# Deckelplatine.net
KiCad netlist of a schematic drawn in EAGLE
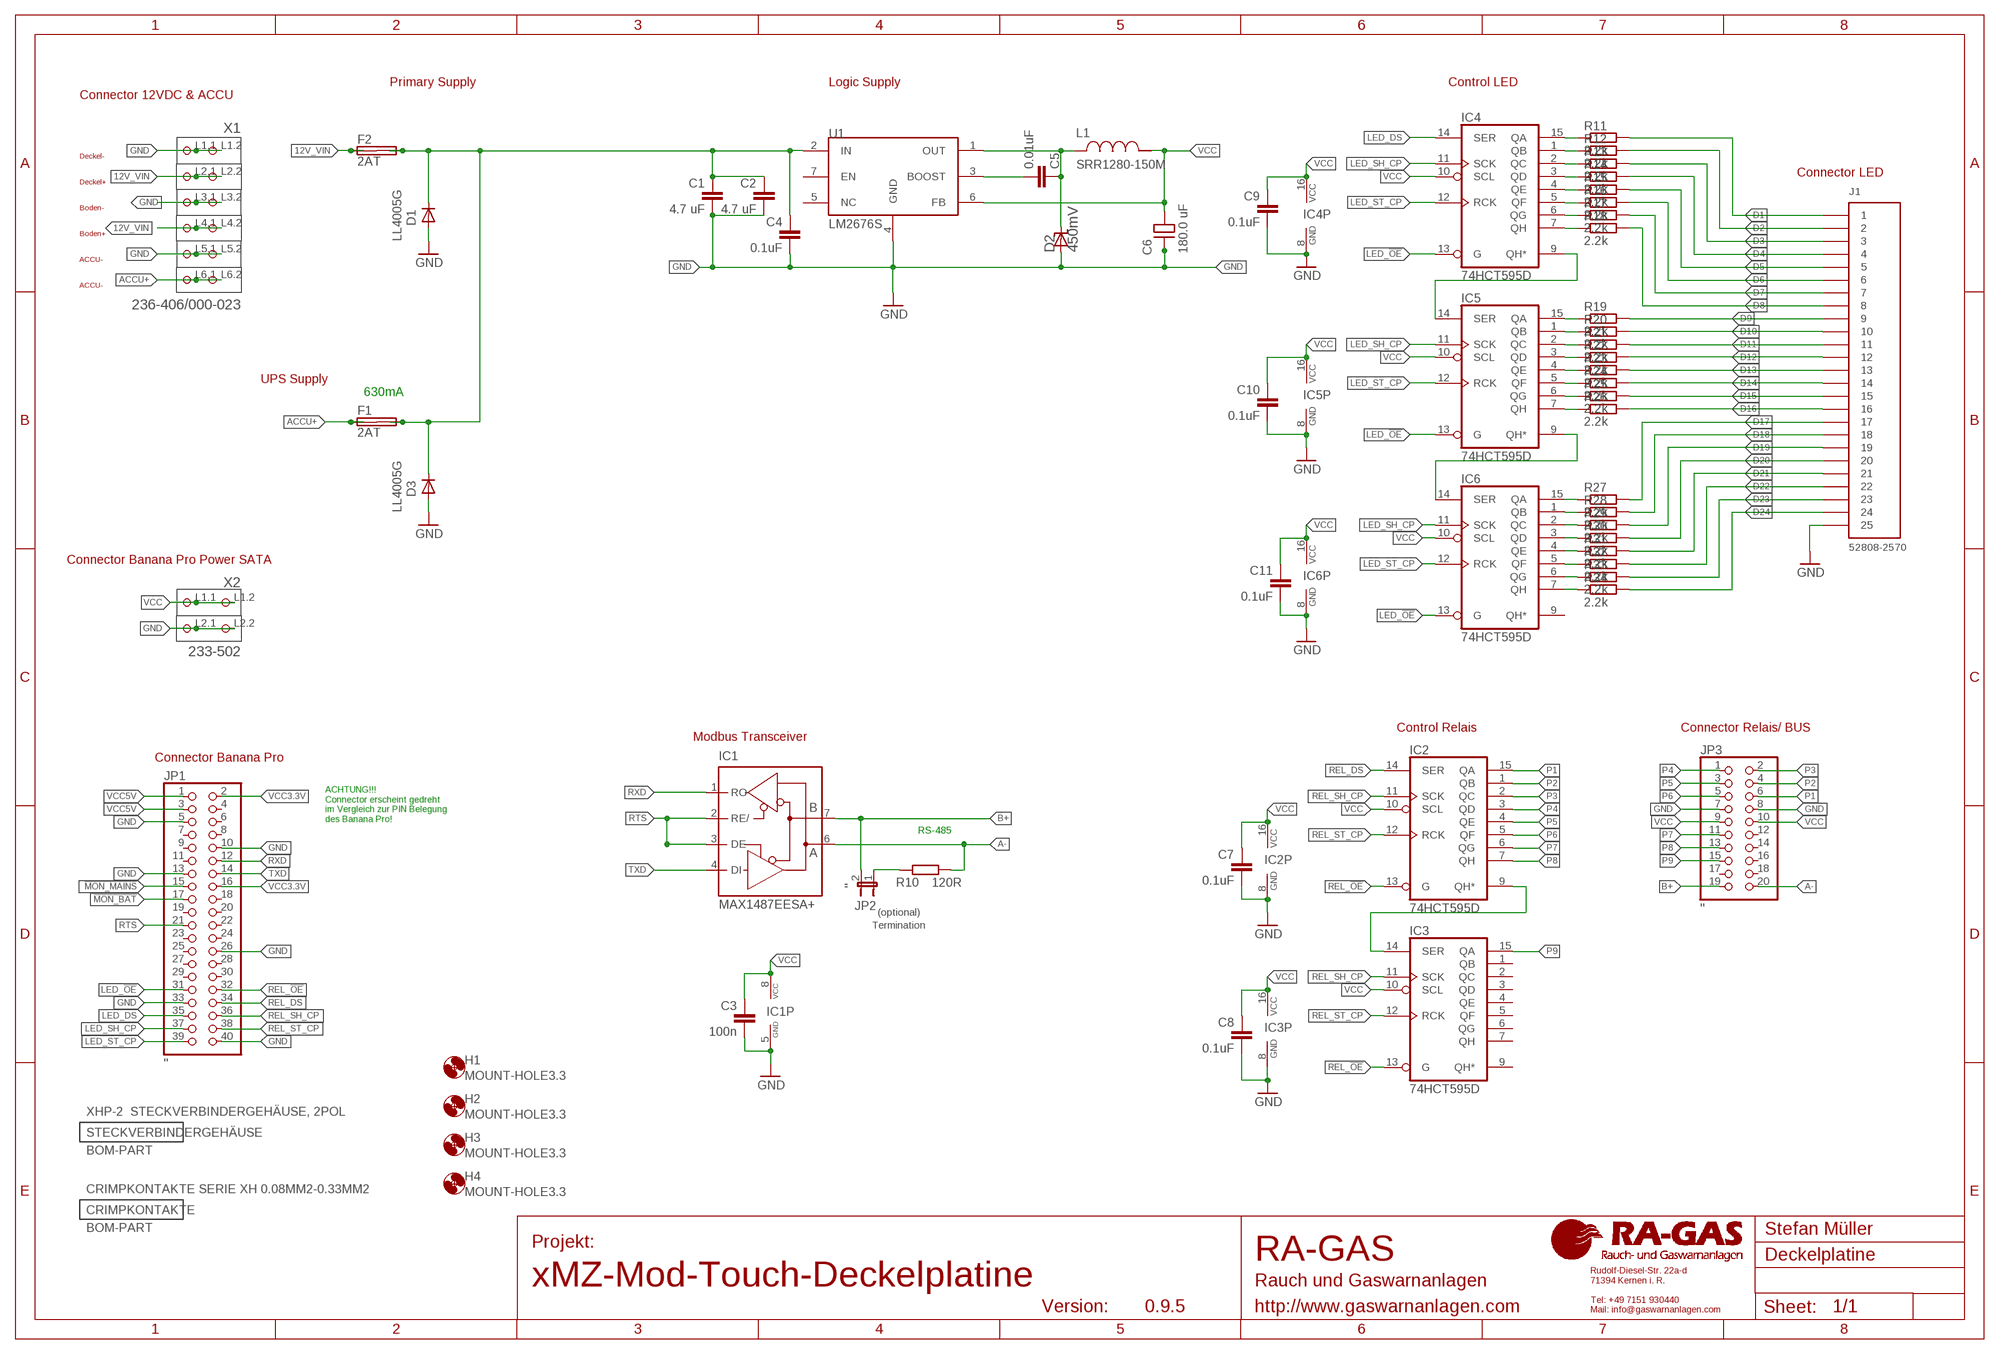
[diagram p0: schematic, sheet 1]

(export (version "E")
  (design (tool "Eeschema 10.0.6"))
  (components
    (comp (ref "C1")
      (value "4.7 uF")
      (footprint "eagle-import:GRM21BR61E475MA12L")
      (fields (field (name "MANUFACTURER_PART_NUMBER") "GRM21BR61E475MA12L") (field (name "MF") "MURATA"))
      (libsource (lib "eagle-import") (part "GRM21BR61E475MA12L"))
    )
    (comp (ref "C2")
      (value "4.7 uF")
      (footprint "eagle-import:GRM21BR61E475MA12L")
      (fields (field (name "MANUFACTURER_PART_NUMBER") "GRM21BR61E475MA12L") (field (name "MF") "MURATA"))
      (libsource (lib "eagle-import") (part "GRM21BR61E475MA12L"))
    )
    (comp (ref "C3")
      (value "100n")
      (footprint "eagle-import:C0603")
      (fields
        (field (name "MF") "KEMET")
        (field (name "MPN") "C0603C104K8RACTU")
        (field (name "PARTNO") "ECHU-16-100N")
      )
      (libsource (lib "eagle-import") (part "C-EUC0603"))
    )
    (comp (ref "C4")
      (value "0.1uF")
      (footprint "eagle-import:0805")
      (fields (field (name "MANUFACTURER_PART_NUMBER") "08053C104KAT2A") (field (name "MF") "AVX"))
      (libsource (lib "eagle-import") (part "08053C104KAT2A"))
    )
    (comp (ref "C5")
      (value "0.01uF")
      (footprint "eagle-import:GRM216R71H103KA01D")
      (fields (field (name "MANUFACTURER_PART_NUMBER") "GRM216R71H103KA01D") (field (name "MF") "MURATA"))
      (libsource (lib "eagle-import") (part "GRM216R71H103KA01D"))
    )
    (comp (ref "C6")
      (value "180.0 uF")
      (footprint "eagle-import:SM_RADIAL_10MM")
      (fields
        (field (name "MF") "PANASONIC ELECTRONIC COMPONENTS")
        (field (name "MPN") "16SVP180MX")
        (field (name "PARTNO") "RAD FC 560/35")
      )
      (libsource (lib "eagle-import") (part "16SVP180MSM_RADIAL_10MM"))
    )
    (comp (ref "C7")
      (value "0.1uF")
      (footprint "eagle-import:C0603")
      (fields
        (field (name "MF") "KEMET")
        (field (name "MPN") "C0603C104K8RACTU")
        (field (name "PARTNO") "SMD TAN.0,1/35")
      )
      (libsource (lib "eagle-import") (part "C-EUC0603"))
    )
    (comp (ref "C8")
      (value "0.1uF")
      (footprint "eagle-import:C0603")
      (fields
        (field (name "MF") "KEMET")
        (field (name "MPN") "C0603C104K8RACTU")
        (field (name "PARTNO") "SMD TAN.0,1/35")
      )
      (libsource (lib "eagle-import") (part "C-EUC0603"))
    )
    (comp (ref "C9")
      (value "0.1uF")
      (footprint "eagle-import:C0603")
      (fields
        (field (name "MF") "KEMET")
        (field (name "MPN") "C0603C104K8RACTU")
        (field (name "PARTNO") "SMD TAN.0,1/35")
      )
      (libsource (lib "eagle-import") (part "C-EUC0603"))
    )
    (comp (ref "C10")
      (value "0.1uF")
      (footprint "eagle-import:C0603")
      (fields
        (field (name "MF") "KEMET")
        (field (name "MPN") "C0603C104K8RACTU")
        (field (name "PARTNO") "SMD TAN.0,1/35")
      )
      (libsource (lib "eagle-import") (part "C-EUC0603"))
    )
    (comp (ref "C11")
      (value "0.1uF")
      (footprint "eagle-import:C0603")
      (fields
        (field (name "MF") "KEMET")
        (field (name "MPN") "C0603C104K8RACTU")
        (field (name "PARTNO") "SMD TAN.0,1/35")
      )
      (libsource (lib "eagle-import") (part "C-EUC0603"))
    )
    (comp (ref "D1")
      (value "LL4005G")
      (footprint "eagle-import:MELF-MLL41")
      (fields (field (name "MF") "TAIWAN SEMICONDUCTOR"))
      (libsource (lib "eagle-import") (part "DIODE-MELF-MLL41"))
    )
    (comp (ref "D2")
      (value "450mV")
      (footprint "eagle-import:SMB")
      (fields (field (name "MANUFACTURER_PART_NUMBER") "B340LB-13-F") (field (name "MF") "DIODES INC."))
      (libsource (lib "eagle-import") (part "B340LB-13-F"))
    )
    (comp (ref "D3")
      (value "LL4005G")
      (footprint "eagle-import:MELF-MLL41")
      (fields (field (name "MF") "TAIWAN SEMICONDUCTOR"))
      (libsource (lib "eagle-import") (part "DIODE-MELF-MLL41"))
    )
    (comp (ref "F1")
      (value "2AT")
      (footprint "eagle-import:01110005MR")
      (fields (field (name "MF") "LITTELFUSE") (field (name "MPN") "01110005MR"))
      (libsource (lib "eagle-import") (part "01110005MR"))
    )
    (comp (ref "F2")
      (value "2AT")
      (footprint "eagle-import:01110005MR")
      (fields (field (name "MF") "LITTELFUSE") (field (name "MPN") "01110005MR"))
      (libsource (lib "eagle-import") (part "01110005MR"))
    )
    (comp (ref "H1")
      (value "MOUNT-HOLE3.3")
      (footprint "eagle-import:3,3")
      (libsource (lib "eagle-import") (part "MOUNT-HOLE3.3"))
    )
    (comp (ref "H2")
      (value "MOUNT-HOLE3.3")
      (footprint "eagle-import:3,3")
      (libsource (lib "eagle-import") (part "MOUNT-HOLE3.3"))
    )
    (comp (ref "H3")
      (value "MOUNT-HOLE3.3")
      (footprint "eagle-import:3,3")
      (libsource (lib "eagle-import") (part "MOUNT-HOLE3.3"))
    )
    (comp (ref "H4")
      (value "MOUNT-HOLE3.3")
      (footprint "eagle-import:3,3")
      (libsource (lib "eagle-import") (part "MOUNT-HOLE3.3"))
    )
    (comp (ref "IC1")
      (value "MAX1487EESA+")
      (footprint "eagle-import:SO08")
      (fields
        (field (name "MF") "MAXIM")
        (field (name "MPN") "MAX481CSA")
        (field (name "MF_1") "MAXIM INTEGRATED PRODUCTS")
        (field (name "MPN_1") "MAX1487EESA+")
        (field (name "OC_FARNELL") "1593310")
        (field (name "PARTNO") "MAX481CSA")
      )
      (libsource (lib "eagle-import") (part "MAX481CSA"))
    )
    (comp (ref "IC2")
      (value "74HCT595D")
      (footprint "eagle-import:SO16")
      (fields
        (field (name "MF") "NXP")
        (field (name "PARTNO") "SMD HC 595")
        (field (name "MPN") "74HCT595D")
        (field (name "OC_FARNELL") "2098004")
      )
      (libsource (lib "eagle-import") (part "74595DHCT"))
    )
    (comp (ref "IC3")
      (value "74HCT595D")
      (footprint "eagle-import:SO16")
      (fields
        (field (name "MF") "NXP")
        (field (name "MPN") "74HCT595D")
        (field (name "OC_FARNELL") "2098004")
        (field (name "PARTNO") "SMD HC 595")
      )
      (libsource (lib "eagle-import") (part "74595DHCT"))
    )
    (comp (ref "IC4")
      (value "74HCT595D")
      (footprint "eagle-import:SO16")
      (fields
        (field (name "MF") "NXP")
        (field (name "MPN") "74HCT595D")
        (field (name "OC_FARNELL") "2098004")
        (field (name "PARTNO") "SMD HC 595")
      )
      (libsource (lib "eagle-import") (part "74595DHCT"))
    )
    (comp (ref "IC5")
      (value "74HCT595D")
      (footprint "eagle-import:SO16")
      (fields
        (field (name "MF") "NXP")
        (field (name "MPN") "74HCT595D")
        (field (name "OC_FARNELL") "2098004")
        (field (name "PARTNO") "SMD HC 595")
      )
      (libsource (lib "eagle-import") (part "74595DHCT"))
    )
    (comp (ref "IC6")
      (value "74HCT595D")
      (footprint "eagle-import:SO16")
      (fields
        (field (name "MF") "NXP")
        (field (name "MPN") "74HCT595D")
        (field (name "OC_FARNELL") "2098004")
        (field (name "PARTNO") "SMD HC 595")
      )
      (libsource (lib "eagle-import") (part "74595DHCT"))
    )
    (comp (ref "J1")
      (value "52808-2570")
      (footprint "eagle-import:52808-2570")
      (fields (field (name "MF") "MOLEX"))
      (libsource (lib "eagle-import") (part "52808-2570"))
    )
    (comp (ref "JP1")
      (value "''")
      (footprint "eagle-import:2X20")
      (fields (field (name "MF") "HARWIN") (field (name "MPN") "M20-6112045"))
      (libsource (lib "eagle-import") (part "PINHD-2X20"))
    )
    (comp (ref "JP2")
      (value "''")
      (footprint "eagle-import:JP1")
      (fields (field (name "MF") "TE CONNECTIVITY / AMP") (field (name "MPN") "825433-2"))
      (libsource (lib "eagle-import") (part "JP1E"))
    )
    (comp (ref "JP3")
      (value "''")
      (footprint "eagle-import:2X10")
      (fields (field (name "MF") "TE CONNECTIVITY / AMP") (field (name "MPN") "5103308-5"))
      (libsource (lib "eagle-import") (part "PINHD-2X10"))
    )
    (comp (ref "L1")
      (value "SRR1280-150M")
      (footprint "eagle-import:SRR1280")
      (fields (field (name "MF") "COILCRAFT") (field (name "MPN") "MSS1278-153MLD"))
      (libsource (lib "eagle-import") (part "SRR1280-150M"))
    )
    (comp (ref "R10")
      (value "120R")
      (footprint "eagle-import:R1206")
      (fields (field (name "MF") "TE CONNECTIVITY") (field (name "MPN") "CRGH1206F120R"))
      (libsource (lib "eagle-import") (part "rcl_R-EU_R1206"))
    )
    (comp (ref "R11")
      (value "2.2k")
      (footprint "eagle-import:R0603")
      (fields
        (field (name "MF") "YAGEO (PHYCOMP)")
        (field (name "MPN") "RC0603FR-072K2L")
        (field (name "PARTNO") "SMD-0603 2,2K")
      )
      (libsource (lib "eagle-import") (part "R-EU_R0603"))
    )
    (comp (ref "R12")
      (value "2.2k")
      (footprint "eagle-import:R0603")
      (fields
        (field (name "MF") "YAGEO (PHYCOMP)")
        (field (name "MPN") "RC0603FR-072K2L")
        (field (name "PARTNO") "SMD-0603 2,2K")
      )
      (libsource (lib "eagle-import") (part "R-EU_R0603"))
    )
    (comp (ref "R13")
      (value "2.2k")
      (footprint "eagle-import:R0603")
      (fields
        (field (name "MF") "YAGEO (PHYCOMP)")
        (field (name "MPN") "RC0603FR-072K2L")
        (field (name "PARTNO") "SMD-0603 2,2K")
      )
      (libsource (lib "eagle-import") (part "R-EU_R0603"))
    )
    (comp (ref "R14")
      (value "2.2k")
      (footprint "eagle-import:R0603")
      (fields
        (field (name "MF") "YAGEO (PHYCOMP)")
        (field (name "MPN") "RC0603FR-072K2L")
        (field (name "PARTNO") "SMD-0603 2,2K")
      )
      (libsource (lib "eagle-import") (part "R-EU_R0603"))
    )
    (comp (ref "R15")
      (value "2.2k")
      (footprint "eagle-import:R0603")
      (fields
        (field (name "MF") "YAGEO (PHYCOMP)")
        (field (name "MPN") "RC0603FR-072K2L")
        (field (name "PARTNO") "SMD-0603 2,2K")
      )
      (libsource (lib "eagle-import") (part "R-EU_R0603"))
    )
    (comp (ref "R16")
      (value "2.2k")
      (footprint "eagle-import:R0603")
      (fields
        (field (name "MF") "YAGEO (PHYCOMP)")
        (field (name "MPN") "RC0603FR-072K2L")
        (field (name "PARTNO") "SMD-0603 2,2K")
      )
      (libsource (lib "eagle-import") (part "R-EU_R0603"))
    )
    (comp (ref "R17")
      (value "2.2k")
      (footprint "eagle-import:R0603")
      (fields
        (field (name "MF") "YAGEO (PHYCOMP)")
        (field (name "MPN") "RC0603FR-072K2L")
        (field (name "PARTNO") "SMD-0603 2,2K")
      )
      (libsource (lib "eagle-import") (part "R-EU_R0603"))
    )
    (comp (ref "R18")
      (value "2.2k")
      (footprint "eagle-import:R0603")
      (fields
        (field (name "MF") "YAGEO (PHYCOMP)")
        (field (name "MPN") "RC0603FR-072K2L")
        (field (name "PARTNO") "SMD-0603 2,2K")
      )
      (libsource (lib "eagle-import") (part "R-EU_R0603"))
    )
    (comp (ref "R19")
      (value "2.2k")
      (footprint "eagle-import:R0603")
      (fields
        (field (name "MF") "YAGEO (PHYCOMP)")
        (field (name "MPN") "RC0603FR-072K2L")
        (field (name "PARTNO") "SMD-0603 2,2K")
      )
      (libsource (lib "eagle-import") (part "R-EU_R0603"))
    )
    (comp (ref "R20")
      (value "2.2k")
      (footprint "eagle-import:R0603")
      (fields
        (field (name "MF") "YAGEO (PHYCOMP)")
        (field (name "MPN") "RC0603FR-072K2L")
        (field (name "PARTNO") "SMD-0603 2,2K")
      )
      (libsource (lib "eagle-import") (part "R-EU_R0603"))
    )
    (comp (ref "R21")
      (value "2.2k")
      (footprint "eagle-import:R0603")
      (fields
        (field (name "MF") "YAGEO (PHYCOMP)")
        (field (name "MPN") "RC0603FR-072K2L")
        (field (name "PARTNO") "SMD-0603 2,2K")
      )
      (libsource (lib "eagle-import") (part "R-EU_R0603"))
    )
    (comp (ref "R22")
      (value "2.2k")
      (footprint "eagle-import:R0603")
      (fields
        (field (name "MF") "YAGEO (PHYCOMP)")
        (field (name "MPN") "RC0603FR-072K2L")
        (field (name "PARTNO") "SMD-0603 2,2K")
      )
      (libsource (lib "eagle-import") (part "R-EU_R0603"))
    )
    (comp (ref "R23")
      (value "2.2k")
      (footprint "eagle-import:R0603")
      (fields
        (field (name "MF") "YAGEO (PHYCOMP)")
        (field (name "MPN") "RC0603FR-072K2L")
        (field (name "PARTNO") "SMD-0603 2,2K")
      )
      (libsource (lib "eagle-import") (part "R-EU_R0603"))
    )
    (comp (ref "R24")
      (value "2.2k")
      (footprint "eagle-import:R0603")
      (fields
        (field (name "MF") "YAGEO (PHYCOMP)")
        (field (name "MPN") "RC0603FR-072K2L")
        (field (name "PARTNO") "SMD-0603 2,2K")
      )
      (libsource (lib "eagle-import") (part "R-EU_R0603"))
    )
    (comp (ref "R25")
      (value "2.2k")
      (footprint "eagle-import:R0603")
      (fields
        (field (name "MF") "YAGEO (PHYCOMP)")
        (field (name "MPN") "RC0603FR-072K2L")
        (field (name "PARTNO") "SMD-0603 2,2K")
      )
      (libsource (lib "eagle-import") (part "R-EU_R0603"))
    )
    (comp (ref "R26")
      (value "2.2k")
      (footprint "eagle-import:R0603")
      (fields
        (field (name "MF") "YAGEO (PHYCOMP)")
        (field (name "MPN") "RC0603FR-072K2L")
        (field (name "PARTNO") "SMD-0603 2,2K")
      )
      (libsource (lib "eagle-import") (part "R-EU_R0603"))
    )
    (comp (ref "R27")
      (value "2.2k")
      (footprint "eagle-import:R0603")
      (fields
        (field (name "MF") "YAGEO (PHYCOMP)")
        (field (name "MPN") "RC0603FR-072K2L")
        (field (name "PARTNO") "SMD-0603 2,2K")
      )
      (libsource (lib "eagle-import") (part "R-EU_R0603"))
    )
    (comp (ref "R28")
      (value "2.2k")
      (footprint "eagle-import:R0603")
      (fields
        (field (name "MF") "YAGEO (PHYCOMP)")
        (field (name "MPN") "RC0603FR-072K2L")
        (field (name "PARTNO") "SMD-0603 2,2K")
      )
      (libsource (lib "eagle-import") (part "R-EU_R0603"))
    )
    (comp (ref "R29")
      (value "2.2k")
      (footprint "eagle-import:R0603")
      (fields
        (field (name "MF") "YAGEO (PHYCOMP)")
        (field (name "MPN") "RC0603FR-072K2L")
        (field (name "PARTNO") "SMD-0603 2,2K")
      )
      (libsource (lib "eagle-import") (part "R-EU_R0603"))
    )
    (comp (ref "R30")
      (value "2.2k")
      (footprint "eagle-import:R0603")
      (fields
        (field (name "MF") "YAGEO (PHYCOMP)")
        (field (name "MPN") "RC0603FR-072K2L")
        (field (name "PARTNO") "SMD-0603 2,2K")
      )
      (libsource (lib "eagle-import") (part "R-EU_R0603"))
    )
    (comp (ref "R31")
      (value "2.2k")
      (footprint "eagle-import:R0603")
      (fields
        (field (name "MF") "YAGEO (PHYCOMP)")
        (field (name "MPN") "RC0603FR-072K2L")
        (field (name "PARTNO") "SMD-0603 2,2K")
      )
      (libsource (lib "eagle-import") (part "R-EU_R0603"))
    )
    (comp (ref "R32")
      (value "2.2k")
      (footprint "eagle-import:R0603")
      (fields
        (field (name "MF") "YAGEO (PHYCOMP)")
        (field (name "MPN") "RC0603FR-072K2L")
        (field (name "PARTNO") "SMD-0603 2,2K")
      )
      (libsource (lib "eagle-import") (part "R-EU_R0603"))
    )
    (comp (ref "R33")
      (value "2.2k")
      (footprint "eagle-import:R0603")
      (fields
        (field (name "MF") "YAGEO (PHYCOMP)")
        (field (name "MPN") "RC0603FR-072K2L")
        (field (name "PARTNO") "SMD-0603 2,2K")
      )
      (libsource (lib "eagle-import") (part "R-EU_R0603"))
    )
    (comp (ref "R34")
      (value "2.2k")
      (footprint "eagle-import:R0603")
      (fields
        (field (name "MF") "YAGEO (PHYCOMP)")
        (field (name "MPN") "RC0603FR-072K2L")
        (field (name "PARTNO") "SMD-0603 2,2K")
      )
      (libsource (lib "eagle-import") (part "R-EU_R0603"))
    )
    (comp (ref "U1")
      (value "LM2676S")
      (footprint "eagle-import:TO-263-7")
      (fields (field (name "MF") "TEXAS INSTRUMENTS") (field (name "MPN") "LM2676S-5.0/NOPB"))
      (libsource (lib "eagle-import") (part "LM2676S"))
    )
    (comp (ref "X1")
      (value "236-406/000-023")
      (footprint "eagle-import:P-236-406")
      (fields (field (name "MF") "WAGO") (field (name "MPN") "236-406"))
      (libsource (lib "eagle-import") (part "236-406/000-023"))
    )
    (comp (ref "X2")
      (value "233-502")
      (footprint "eagle-import:P-233-502")
      (fields (field (name "MF") "WAGO") (field (name "MPN") "233-502."))
      (libsource (lib "eagle-import") (part "233-502"))
    )
  )
  (nets
    (net (code "1") (name "/LED_~{OE}") (class "Default")
      (node (ref "IC4") (pin "13") (pinfunction "G_13") (pintype "input"))
      (node (ref "IC5") (pin "13") (pinfunction "G_13") (pintype "input"))
      (node (ref "IC6") (pin "13") (pinfunction "G_13") (pintype "input"))
      (node (ref "JP1") (pin "31") (pinfunction "31_31") (pintype "passive"))
    )
    (net (code "2") (name "/REL_~{OE}") (class "Default")
      (node (ref "IC2") (pin "13") (pinfunction "G_13") (pintype "input"))
      (node (ref "IC3") (pin "13") (pinfunction "G_13") (pintype "input"))
      (node (ref "JP1") (pin "32") (pinfunction "32_32") (pintype "passive"))
    )
    (net (code "3") (name "/~{MON_BAT}") (class "Default")
      (node (ref "JP1") (pin "17") (pinfunction "17_17") (pintype "passive"))
    )
    (net (code "4") (name "/~{MON_MAINS}") (class "Default")
      (node (ref "JP1") (pin "15") (pinfunction "15_15") (pintype "passive"))
    )
    (net (code "5") (name "12V_VIN") (class "Default")
      (node (ref "F2") (pin "1A") (pinfunction "1A_1A") (pintype "passive"))
      (node (ref "F2") (pin "1B") (pinfunction "1B_1B") (pintype "passive"))
      (node (ref "X1") (pin "L2.1") (pinfunction "P2.1_L2.1") (pintype "bidirectional"))
      (node (ref "X1") (pin "L2.2") (pinfunction "P2.2_L2.2") (pintype "bidirectional"))
      (node (ref "X1") (pin "L4.1") (pinfunction "P4.1_L4.1") (pintype "bidirectional"))
      (node (ref "X1") (pin "L4.2") (pinfunction "P4.2_L4.2") (pintype "bidirectional"))
    )
    (net (code "6") (name "A-") (class "Default")
      (node (ref "IC1") (pin "6") (pinfunction "A_6") (pintype "passive"))
      (node (ref "JP3") (pin "20") (pinfunction "20_20") (pintype "passive"))
      (node (ref "R10") (pin "2") (pinfunction "2_2") (pintype "passive"))
    )
    (net (code "7") (name "ACCU+") (class "Default")
      (node (ref "F1") (pin "1A") (pinfunction "1A_1A") (pintype "passive"))
      (node (ref "F1") (pin "1B") (pinfunction "1B_1B") (pintype "passive"))
      (node (ref "X1") (pin "L6.1") (pinfunction "P6.1_L6.1") (pintype "bidirectional"))
      (node (ref "X1") (pin "L6.2") (pinfunction "P6.2_L6.2") (pintype "bidirectional"))
    )
    (net (code "8") (name "B+") (class "Default")
      (node (ref "IC1") (pin "7") (pinfunction "B_7") (pintype "passive"))
      (node (ref "JP2") (pin "2") (pinfunction "2_2") (pintype "passive"))
      (node (ref "JP3") (pin "19") (pinfunction "19_19") (pintype "passive"))
    )
    (net (code "9") (name "D1") (class "Default")
      (node (ref "J1") (pin "1") (pinfunction "1_1") (pintype "bidirectional"))
      (node (ref "R11") (pin "2") (pinfunction "2_2") (pintype "passive"))
    )
    (net (code "10") (name "D2") (class "Default")
      (node (ref "J1") (pin "2") (pinfunction "2_2") (pintype "bidirectional"))
      (node (ref "R12") (pin "2") (pinfunction "2_2") (pintype "passive"))
    )
    (net (code "11") (name "D3") (class "Default")
      (node (ref "J1") (pin "3") (pinfunction "3_3") (pintype "bidirectional"))
      (node (ref "R13") (pin "2") (pinfunction "2_2") (pintype "passive"))
    )
    (net (code "12") (name "D4") (class "Default")
      (node (ref "J1") (pin "4") (pinfunction "4_4") (pintype "bidirectional"))
      (node (ref "R14") (pin "2") (pinfunction "2_2") (pintype "passive"))
    )
    (net (code "13") (name "D5") (class "Default")
      (node (ref "J1") (pin "5") (pinfunction "5_5") (pintype "bidirectional"))
      (node (ref "R15") (pin "2") (pinfunction "2_2") (pintype "passive"))
    )
    (net (code "14") (name "D6") (class "Default")
      (node (ref "J1") (pin "6") (pinfunction "6_6") (pintype "bidirectional"))
      (node (ref "R16") (pin "2") (pinfunction "2_2") (pintype "passive"))
    )
    (net (code "15") (name "D7") (class "Default")
      (node (ref "J1") (pin "7") (pinfunction "7_7") (pintype "bidirectional"))
      (node (ref "R17") (pin "2") (pinfunction "2_2") (pintype "passive"))
    )
    (net (code "16") (name "D8") (class "Default")
      (node (ref "J1") (pin "8") (pinfunction "8_8") (pintype "bidirectional"))
      (node (ref "R18") (pin "2") (pinfunction "2_2") (pintype "passive"))
    )
    (net (code "17") (name "D9") (class "Default")
      (node (ref "J1") (pin "9") (pinfunction "9_9") (pintype "bidirectional"))
      (node (ref "R19") (pin "2") (pinfunction "2_2") (pintype "passive"))
    )
    (net (code "18") (name "D10") (class "Default")
      (node (ref "J1") (pin "10") (pinfunction "10_10") (pintype "bidirectional"))
      (node (ref "R20") (pin "2") (pinfunction "2_2") (pintype "passive"))
    )
    (net (code "19") (name "D11") (class "Default")
      (node (ref "J1") (pin "11") (pinfunction "11_11") (pintype "bidirectional"))
      (node (ref "R21") (pin "2") (pinfunction "2_2") (pintype "passive"))
    )
    (net (code "20") (name "D12") (class "Default")
      (node (ref "J1") (pin "12") (pinfunction "12_12") (pintype "bidirectional"))
      (node (ref "R22") (pin "2") (pinfunction "2_2") (pintype "passive"))
    )
    (net (code "21") (name "D13") (class "Default")
      (node (ref "J1") (pin "13") (pinfunction "13_13") (pintype "bidirectional"))
      (node (ref "R23") (pin "2") (pinfunction "2_2") (pintype "passive"))
    )
    (net (code "22") (name "D14") (class "Default")
      (node (ref "J1") (pin "14") (pinfunction "14_14") (pintype "bidirectional"))
      (node (ref "R24") (pin "2") (pinfunction "2_2") (pintype "passive"))
    )
    (net (code "23") (name "D15") (class "Default")
      (node (ref "J1") (pin "15") (pinfunction "15_15") (pintype "bidirectional"))
      (node (ref "R25") (pin "2") (pinfunction "2_2") (pintype "passive"))
    )
    (net (code "24") (name "D16") (class "Default")
      (node (ref "J1") (pin "16") (pinfunction "16_16") (pintype "bidirectional"))
      (node (ref "R26") (pin "2") (pinfunction "2_2") (pintype "passive"))
    )
    (net (code "25") (name "D17") (class "Default")
      (node (ref "J1") (pin "17") (pinfunction "17_17") (pintype "bidirectional"))
      (node (ref "R27") (pin "2") (pinfunction "2_2") (pintype "passive"))
    )
    (net (code "26") (name "D18") (class "Default")
      (node (ref "J1") (pin "18") (pinfunction "18_18") (pintype "bidirectional"))
      (node (ref "R28") (pin "2") (pinfunction "2_2") (pintype "passive"))
    )
    (net (code "27") (name "D19") (class "Default")
      (node (ref "J1") (pin "19") (pinfunction "19_19") (pintype "bidirectional"))
      (node (ref "R29") (pin "2") (pinfunction "2_2") (pintype "passive"))
    )
    (net (code "28") (name "D20") (class "Default")
      (node (ref "J1") (pin "20") (pinfunction "20_20") (pintype "bidirectional"))
      (node (ref "R30") (pin "2") (pinfunction "2_2") (pintype "passive"))
    )
    (net (code "29") (name "D21") (class "Default")
      (node (ref "J1") (pin "21") (pinfunction "21_21") (pintype "bidirectional"))
      (node (ref "R31") (pin "2") (pinfunction "2_2") (pintype "passive"))
    )
    (net (code "30") (name "D22") (class "Default")
      (node (ref "J1") (pin "22") (pinfunction "22_22") (pintype "bidirectional"))
      (node (ref "R32") (pin "2") (pinfunction "2_2") (pintype "passive"))
    )
    (net (code "31") (name "D23") (class "Default")
      (node (ref "J1") (pin "23") (pinfunction "23_23") (pintype "bidirectional"))
      (node (ref "R33") (pin "2") (pinfunction "2_2") (pintype "passive"))
    )
    (net (code "32") (name "D24") (class "Default")
      (node (ref "J1") (pin "24") (pinfunction "24_24") (pintype "bidirectional"))
      (node (ref "R34") (pin "2") (pinfunction "2_2") (pintype "passive"))
    )
    (net (code "33") (name "GND") (class "Default")
      (node (ref "C1") (pin "2") (pinfunction "2_2") (pintype "passive"))
      (node (ref "C10") (pin "2") (pinfunction "2_2") (pintype "passive"))
      (node (ref "C11") (pin "2") (pinfunction "2_2") (pintype "passive"))
      (node (ref "C2") (pin "2") (pinfunction "2_2") (pintype "passive"))
      (node (ref "C3") (pin "2") (pinfunction "2_2") (pintype "passive"))
      (node (ref "C4") (pin "2") (pinfunction "2_2") (pintype "passive"))
      (node (ref "C6") (pin "2") (pinfunction "-_2") (pintype "passive"))
      (node (ref "C7") (pin "2") (pinfunction "2_2") (pintype "passive"))
      (node (ref "C8") (pin "2") (pinfunction "2_2") (pintype "passive"))
      (node (ref "C9") (pin "2") (pinfunction "2_2") (pintype "passive"))
      (node (ref "D1") (pin "A") (pinfunction "A_A") (pintype "passive"))
      (node (ref "D2") (pin "A") (pinfunction "A_A") (pintype "passive"))
      (node (ref "D3") (pin "A") (pinfunction "A_A") (pintype "passive"))
      (node (ref "IC1") (pin "5") (pinfunction "GND_5") (pintype "power_in"))
      (node (ref "IC2") (pin "8") (pinfunction "GND_8") (pintype "power_in"))
      (node (ref "IC3") (pin "8") (pinfunction "GND_8") (pintype "power_in"))
      (node (ref "IC4") (pin "8") (pinfunction "GND_8") (pintype "power_in"))
      (node (ref "IC5") (pin "8") (pinfunction "GND_8") (pintype "power_in"))
      (node (ref "IC6") (pin "8") (pinfunction "GND_8") (pintype "power_in"))
      (node (ref "J1") (pin "25") (pinfunction "25_25") (pintype "bidirectional"))
      (node (ref "JP1") (pin "10") (pinfunction "10_10") (pintype "passive"))
      (node (ref "JP1") (pin "13") (pinfunction "13_13") (pintype "passive"))
      (node (ref "JP1") (pin "26") (pinfunction "26_26") (pintype "passive"))
      (node (ref "JP1") (pin "33") (pinfunction "33_33") (pintype "passive"))
      (node (ref "JP1") (pin "40") (pinfunction "40_40") (pintype "passive"))
      (node (ref "JP1") (pin "5") (pinfunction "5_5") (pintype "passive"))
      (node (ref "JP3") (pin "7") (pinfunction "7_7") (pintype "passive"))
      (node (ref "JP3") (pin "8") (pinfunction "8_8") (pintype "passive"))
      (node (ref "U1") (pin "4") (pinfunction "GND_4") (pintype "power_in"))
      (node (ref "X1") (pin "L1.1") (pinfunction "P1.1_L1.1") (pintype "bidirectional"))
      (node (ref "X1") (pin "L1.2") (pinfunction "P1.2_L1.2") (pintype "bidirectional"))
      (node (ref "X1") (pin "L3.1") (pinfunction "P3.1_L3.1") (pintype "bidirectional"))
      (node (ref "X1") (pin "L3.2") (pinfunction "P3.2_L3.2") (pintype "bidirectional"))
      (node (ref "X1") (pin "L5.1") (pinfunction "P5.1_L5.1") (pintype "bidirectional"))
      (node (ref "X1") (pin "L5.2") (pinfunction "P5.2_L5.2") (pintype "bidirectional"))
      (node (ref "X2") (pin "L2.1") (pinfunction "P2.1_L2.1") (pintype "bidirectional"))
      (node (ref "X2") (pin "L2.2") (pinfunction "P2.2_L2.2") (pintype "bidirectional"))
    )
    (net (code "34") (name "LED_DS") (class "Default")
      (node (ref "IC4") (pin "14") (pinfunction "SER_14") (pintype "input"))
      (node (ref "JP1") (pin "35") (pinfunction "35_35") (pintype "passive"))
    )
    (net (code "35") (name "LED_SH_CP") (class "Default")
      (node (ref "IC4") (pin "11") (pinfunction "SCK_11") (pintype "input"))
      (node (ref "IC5") (pin "11") (pinfunction "SCK_11") (pintype "input"))
      (node (ref "IC6") (pin "11") (pinfunction "SCK_11") (pintype "input"))
      (node (ref "JP1") (pin "37") (pinfunction "37_37") (pintype "passive"))
    )
    (net (code "36") (name "LED_ST_CP") (class "Default")
      (node (ref "IC4") (pin "12") (pinfunction "RCK_12") (pintype "input"))
      (node (ref "IC5") (pin "12") (pinfunction "RCK_12") (pintype "input"))
      (node (ref "IC6") (pin "12") (pinfunction "RCK_12") (pintype "input"))
      (node (ref "JP1") (pin "39") (pinfunction "39_39") (pintype "passive"))
    )
    (net (code "37") (name "Net-(IC2A-QH*)") (class "Default")
      (node (ref "IC2") (pin "9") (pinfunction "QH*_9") (pintype "tri_state"))
      (node (ref "IC3") (pin "14") (pinfunction "SER_14") (pintype "input"))
    )
    (net (code "38") (name "Net-(IC4A-QA)") (class "Default")
      (node (ref "IC4") (pin "15") (pinfunction "QA_15") (pintype "tri_state"))
      (node (ref "R11") (pin "1") (pinfunction "1_1") (pintype "passive"))
    )
    (net (code "39") (name "Net-(IC4A-QB)") (class "Default")
      (node (ref "IC4") (pin "1") (pinfunction "QB_1") (pintype "tri_state"))
      (node (ref "R12") (pin "1") (pinfunction "1_1") (pintype "passive"))
    )
    (net (code "40") (name "Net-(IC4A-QC)") (class "Default")
      (node (ref "IC4") (pin "2") (pinfunction "QC_2") (pintype "tri_state"))
      (node (ref "R13") (pin "1") (pinfunction "1_1") (pintype "passive"))
    )
    (net (code "41") (name "Net-(IC4A-QD)") (class "Default")
      (node (ref "IC4") (pin "3") (pinfunction "QD_3") (pintype "tri_state"))
      (node (ref "R14") (pin "1") (pinfunction "1_1") (pintype "passive"))
    )
    (net (code "42") (name "Net-(IC4A-QE)") (class "Default")
      (node (ref "IC4") (pin "4") (pinfunction "QE_4") (pintype "tri_state"))
      (node (ref "R15") (pin "1") (pinfunction "1_1") (pintype "passive"))
    )
    (net (code "43") (name "Net-(IC4A-QF)") (class "Default")
      (node (ref "IC4") (pin "5") (pinfunction "QF_5") (pintype "tri_state"))
      (node (ref "R16") (pin "1") (pinfunction "1_1") (pintype "passive"))
    )
    (net (code "44") (name "Net-(IC4A-QG)") (class "Default")
      (node (ref "IC4") (pin "6") (pinfunction "QG_6") (pintype "tri_state"))
      (node (ref "R17") (pin "1") (pinfunction "1_1") (pintype "passive"))
    )
    (net (code "45") (name "Net-(IC4A-QH)") (class "Default")
      (node (ref "IC4") (pin "7") (pinfunction "QH_7") (pintype "tri_state"))
      (node (ref "R18") (pin "1") (pinfunction "1_1") (pintype "passive"))
    )
    (net (code "46") (name "Net-(IC4A-QH*)") (class "Default")
      (node (ref "IC4") (pin "9") (pinfunction "QH*_9") (pintype "tri_state"))
      (node (ref "IC5") (pin "14") (pinfunction "SER_14") (pintype "input"))
    )
    (net (code "47") (name "Net-(IC5A-QA)") (class "Default")
      (node (ref "IC5") (pin "15") (pinfunction "QA_15") (pintype "tri_state"))
      (node (ref "R19") (pin "1") (pinfunction "1_1") (pintype "passive"))
    )
    (net (code "48") (name "Net-(IC5A-QB)") (class "Default")
      (node (ref "IC5") (pin "1") (pinfunction "QB_1") (pintype "tri_state"))
      (node (ref "R20") (pin "1") (pinfunction "1_1") (pintype "passive"))
    )
    (net (code "49") (name "Net-(IC5A-QC)") (class "Default")
      (node (ref "IC5") (pin "2") (pinfunction "QC_2") (pintype "tri_state"))
      (node (ref "R21") (pin "1") (pinfunction "1_1") (pintype "passive"))
    )
    (net (code "50") (name "Net-(IC5A-QD)") (class "Default")
      (node (ref "IC5") (pin "3") (pinfunction "QD_3") (pintype "tri_state"))
      (node (ref "R22") (pin "1") (pinfunction "1_1") (pintype "passive"))
    )
    (net (code "51") (name "Net-(IC5A-QE)") (class "Default")
      (node (ref "IC5") (pin "4") (pinfunction "QE_4") (pintype "tri_state"))
      (node (ref "R23") (pin "1") (pinfunction "1_1") (pintype "passive"))
    )
    (net (code "52") (name "Net-(IC5A-QF)") (class "Default")
      (node (ref "IC5") (pin "5") (pinfunction "QF_5") (pintype "tri_state"))
      (node (ref "R24") (pin "1") (pinfunction "1_1") (pintype "passive"))
    )
    (net (code "53") (name "Net-(IC5A-QG)") (class "Default")
      (node (ref "IC5") (pin "6") (pinfunction "QG_6") (pintype "tri_state"))
      (node (ref "R25") (pin "1") (pinfunction "1_1") (pintype "passive"))
    )
    (net (code "54") (name "Net-(IC5A-QH)") (class "Default")
      (node (ref "IC5") (pin "7") (pinfunction "QH_7") (pintype "tri_state"))
      (node (ref "R26") (pin "1") (pinfunction "1_1") (pintype "passive"))
    )
    (net (code "55") (name "Net-(IC5A-QH*)") (class "Default")
      (node (ref "IC5") (pin "9") (pinfunction "QH*_9") (pintype "tri_state"))
      (node (ref "IC6") (pin "14") (pinfunction "SER_14") (pintype "input"))
    )
    (net (code "56") (name "Net-(IC6A-QA)") (class "Default")
      (node (ref "IC6") (pin "15") (pinfunction "QA_15") (pintype "tri_state"))
      (node (ref "R27") (pin "1") (pinfunction "1_1") (pintype "passive"))
    )
    (net (code "57") (name "Net-(IC6A-QB)") (class "Default")
      (node (ref "IC6") (pin "1") (pinfunction "QB_1") (pintype "tri_state"))
      (node (ref "R28") (pin "1") (pinfunction "1_1") (pintype "passive"))
    )
    (net (code "58") (name "Net-(IC6A-QC)") (class "Default")
      (node (ref "IC6") (pin "2") (pinfunction "QC_2") (pintype "tri_state"))
      (node (ref "R29") (pin "1") (pinfunction "1_1") (pintype "passive"))
    )
    (net (code "59") (name "Net-(IC6A-QD)") (class "Default")
      (node (ref "IC6") (pin "3") (pinfunction "QD_3") (pintype "tri_state"))
      (node (ref "R30") (pin "1") (pinfunction "1_1") (pintype "passive"))
    )
    (net (code "60") (name "Net-(IC6A-QE)") (class "Default")
      (node (ref "IC6") (pin "4") (pinfunction "QE_4") (pintype "tri_state"))
      (node (ref "R31") (pin "1") (pinfunction "1_1") (pintype "passive"))
    )
    (net (code "61") (name "Net-(IC6A-QF)") (class "Default")
      (node (ref "IC6") (pin "5") (pinfunction "QF_5") (pintype "tri_state"))
      (node (ref "R32") (pin "1") (pinfunction "1_1") (pintype "passive"))
    )
    (net (code "62") (name "Net-(IC6A-QG)") (class "Default")
      (node (ref "IC6") (pin "6") (pinfunction "QG_6") (pintype "tri_state"))
      (node (ref "R33") (pin "1") (pinfunction "1_1") (pintype "passive"))
    )
    (net (code "63") (name "Net-(IC6A-QH)") (class "Default")
      (node (ref "IC6") (pin "7") (pinfunction "QH_7") (pintype "tri_state"))
      (node (ref "R34") (pin "1") (pinfunction "1_1") (pintype "passive"))
    )
    (net (code "64") (name "Net-(JP2-Pad1)") (class "Default")
      (node (ref "JP2") (pin "1") (pinfunction "1_1") (pintype "passive"))
      (node (ref "R10") (pin "1") (pinfunction "1_1") (pintype "passive"))
    )
    (net (code "65") (name "Net-(U1-BOOST)") (class "Default")
      (node (ref "C5") (pin "2") (pinfunction "2_2") (pintype "passive"))
      (node (ref "U1") (pin "3") (pinfunction "BOOST_3") (pintype "bidirectional"))
    )
    (net (code "66") (name "Net-(U1-IN)") (class "Default")
      (node (ref "C1") (pin "1") (pinfunction "1_1") (pintype "passive"))
      (node (ref "C2") (pin "1") (pinfunction "1_1") (pintype "passive"))
      (node (ref "C4") (pin "1") (pinfunction "1_1") (pintype "passive"))
      (node (ref "D1") (pin "C") (pinfunction "C_C") (pintype "passive"))
      (node (ref "D3") (pin "C") (pinfunction "C_C") (pintype "passive"))
      (node (ref "F1") (pin "2A") (pinfunction "2A_2A") (pintype "passive"))
      (node (ref "F1") (pin "2B") (pinfunction "2B_2B") (pintype "passive"))
      (node (ref "F2") (pin "2A") (pinfunction "2A_2A") (pintype "passive"))
      (node (ref "F2") (pin "2B") (pinfunction "2B_2B") (pintype "passive"))
      (node (ref "U1") (pin "2") (pinfunction "IN_2") (pintype "power_in"))
    )
    (net (code "67") (name "Net-(U1-OUT)") (class "Default")
      (node (ref "C5") (pin "1") (pinfunction "1_1") (pintype "passive"))
      (node (ref "D2") (pin "C") (pinfunction "C_C") (pintype "passive"))
      (node (ref "L1") (pin "1") (pinfunction "1_1") (pintype "passive"))
      (node (ref "U1") (pin "1") (pinfunction "OUT_1") (pintype "bidirectional"))
    )
    (net (code "68") (name "P1") (class "Default")
      (node (ref "IC2") (pin "15") (pinfunction "QA_15") (pintype "tri_state"))
      (node (ref "JP3") (pin "6") (pinfunction "6_6") (pintype "passive"))
    )
    (net (code "69") (name "P2") (class "Default")
      (node (ref "IC2") (pin "1") (pinfunction "QB_1") (pintype "tri_state"))
      (node (ref "JP3") (pin "4") (pinfunction "4_4") (pintype "passive"))
    )
    (net (code "70") (name "P3") (class "Default")
      (node (ref "IC2") (pin "2") (pinfunction "QC_2") (pintype "tri_state"))
      (node (ref "JP3") (pin "2") (pinfunction "2_2") (pintype "passive"))
    )
    (net (code "71") (name "P4") (class "Default")
      (node (ref "IC2") (pin "3") (pinfunction "QD_3") (pintype "tri_state"))
      (node (ref "JP3") (pin "1") (pinfunction "1_1") (pintype "passive"))
    )
    (net (code "72") (name "P5") (class "Default")
      (node (ref "IC2") (pin "4") (pinfunction "QE_4") (pintype "tri_state"))
      (node (ref "JP3") (pin "3") (pinfunction "3_3") (pintype "passive"))
    )
    (net (code "73") (name "P6") (class "Default")
      (node (ref "IC2") (pin "5") (pinfunction "QF_5") (pintype "tri_state"))
      (node (ref "JP3") (pin "5") (pinfunction "5_5") (pintype "passive"))
    )
    (net (code "74") (name "P7") (class "Default")
      (node (ref "IC2") (pin "6") (pinfunction "QG_6") (pintype "tri_state"))
      (node (ref "JP3") (pin "11") (pinfunction "11_11") (pintype "passive"))
    )
    (net (code "75") (name "P8") (class "Default")
      (node (ref "IC2") (pin "7") (pinfunction "QH_7") (pintype "tri_state"))
      (node (ref "JP3") (pin "13") (pinfunction "13_13") (pintype "passive"))
    )
    (net (code "76") (name "P9") (class "Default")
      (node (ref "IC3") (pin "15") (pinfunction "QA_15") (pintype "tri_state"))
      (node (ref "JP3") (pin "15") (pinfunction "15_15") (pintype "passive"))
    )
    (net (code "77") (name "REL_DS") (class "Default")
      (node (ref "IC2") (pin "14") (pinfunction "SER_14") (pintype "input"))
      (node (ref "JP1") (pin "34") (pinfunction "34_34") (pintype "passive"))
    )
    (net (code "78") (name "REL_SH_CP") (class "Default")
      (node (ref "IC2") (pin "11") (pinfunction "SCK_11") (pintype "input"))
      (node (ref "IC3") (pin "11") (pinfunction "SCK_11") (pintype "input"))
      (node (ref "JP1") (pin "36") (pinfunction "36_36") (pintype "passive"))
    )
    (net (code "79") (name "REL_ST_CP") (class "Default")
      (node (ref "IC2") (pin "12") (pinfunction "RCK_12") (pintype "input"))
      (node (ref "IC3") (pin "12") (pinfunction "RCK_12") (pintype "input"))
      (node (ref "JP1") (pin "38") (pinfunction "38_38") (pintype "passive"))
    )
    (net (code "80") (name "RTS") (class "Default")
      (node (ref "IC1") (pin "2") (pinfunction "RE/_2") (pintype "input"))
      (node (ref "IC1") (pin "3") (pinfunction "DE_3") (pintype "input"))
      (node (ref "JP1") (pin "21") (pinfunction "21_21") (pintype "passive"))
    )
    (net (code "81") (name "RXD") (class "Default")
      (node (ref "IC1") (pin "1") (pinfunction "RO_1") (pintype "output"))
      (node (ref "JP1") (pin "12") (pinfunction "12_12") (pintype "passive"))
    )
    (net (code "82") (name "TXD") (class "Default")
      (node (ref "IC1") (pin "4") (pinfunction "DI_4") (pintype "input"))
      (node (ref "JP1") (pin "14") (pinfunction "14_14") (pintype "passive"))
    )
    (net (code "83") (name "VCC") (class "Default")
      (node (ref "C10") (pin "1") (pinfunction "1_1") (pintype "passive"))
      (node (ref "C11") (pin "1") (pinfunction "1_1") (pintype "passive"))
      (node (ref "C3") (pin "1") (pinfunction "1_1") (pintype "passive"))
      (node (ref "C6") (pin "1") (pinfunction "+_1") (pintype "passive"))
      (node (ref "C7") (pin "1") (pinfunction "1_1") (pintype "passive"))
      (node (ref "C8") (pin "1") (pinfunction "1_1") (pintype "passive"))
      (node (ref "C9") (pin "1") (pinfunction "1_1") (pintype "passive"))
      (node (ref "IC1") (pin "8") (pinfunction "VCC_8") (pintype "power_in"))
      (node (ref "IC2") (pin "10") (pinfunction "SCL_10") (pintype "input"))
      (node (ref "IC2") (pin "16") (pinfunction "VCC_16") (pintype "power_in"))
      (node (ref "IC3") (pin "10") (pinfunction "SCL_10") (pintype "input"))
      (node (ref "IC3") (pin "16") (pinfunction "VCC_16") (pintype "power_in"))
      (node (ref "IC4") (pin "10") (pinfunction "SCL_10") (pintype "input"))
      (node (ref "IC4") (pin "16") (pinfunction "VCC_16") (pintype "power_in"))
      (node (ref "IC5") (pin "10") (pinfunction "SCL_10") (pintype "input"))
      (node (ref "IC5") (pin "16") (pinfunction "VCC_16") (pintype "power_in"))
      (node (ref "IC6") (pin "10") (pinfunction "SCL_10") (pintype "input"))
      (node (ref "IC6") (pin "16") (pinfunction "VCC_16") (pintype "power_in"))
      (node (ref "JP3") (pin "10") (pinfunction "10_10") (pintype "passive"))
      (node (ref "JP3") (pin "9") (pinfunction "9_9") (pintype "passive"))
      (node (ref "L1") (pin "2") (pinfunction "2_2") (pintype "passive"))
      (node (ref "U1") (pin "6") (pinfunction "FB_6") (pintype "bidirectional"))
      (node (ref "X2") (pin "L1.1") (pinfunction "P1.1_L1.1") (pintype "bidirectional"))
      (node (ref "X2") (pin "L1.2") (pinfunction "P1.2_L1.2") (pintype "bidirectional"))
    )
    (net (code "84") (name "VCC3.3V") (class "Default")
      (node (ref "JP1") (pin "16") (pinfunction "16_16") (pintype "passive"))
      (node (ref "JP1") (pin "2") (pinfunction "2_2") (pintype "passive"))
    )
    (net (code "85") (name "VCC5V") (class "Default")
      (node (ref "JP1") (pin "1") (pinfunction "1_1") (pintype "passive"))
      (node (ref "JP1") (pin "3") (pinfunction "3_3") (pintype "passive"))
    )
    (net (code "86") (name "unconnected-(IC3A-QB-Pad1)") (class "Default")
      (node (ref "IC3") (pin "1") (pinfunction "QB_1") (pintype "tri_state"))
    )
    (net (code "87") (name "unconnected-(IC3A-QC-Pad2)") (class "Default")
      (node (ref "IC3") (pin "2") (pinfunction "QC_2") (pintype "tri_state"))
    )
    (net (code "88") (name "unconnected-(IC3A-QD-Pad3)") (class "Default")
      (node (ref "IC3") (pin "3") (pinfunction "QD_3") (pintype "tri_state"))
    )
    (net (code "89") (name "unconnected-(IC3A-QE-Pad4)") (class "Default")
      (node (ref "IC3") (pin "4") (pinfunction "QE_4") (pintype "tri_state"))
    )
    (net (code "90") (name "unconnected-(IC3A-QF-Pad5)") (class "Default")
      (node (ref "IC3") (pin "5") (pinfunction "QF_5") (pintype "tri_state"))
    )
    (net (code "91") (name "unconnected-(IC3A-QG-Pad6)") (class "Default")
      (node (ref "IC3") (pin "6") (pinfunction "QG_6") (pintype "tri_state"))
    )
    (net (code "92") (name "unconnected-(IC3A-QH*-Pad9)") (class "Default")
      (node (ref "IC3") (pin "9") (pinfunction "QH*_9") (pintype "tri_state"))
    )
    (net (code "93") (name "unconnected-(IC3A-QH-Pad7)") (class "Default")
      (node (ref "IC3") (pin "7") (pinfunction "QH_7") (pintype "tri_state"))
    )
    (net (code "94") (name "unconnected-(IC6A-QH*-Pad9)") (class "Default")
      (node (ref "IC6") (pin "9") (pinfunction "QH*_9") (pintype "tri_state"))
    )
    (net (code "95") (name "unconnected-(JP1-Pad4)") (class "Default")
      (node (ref "JP1") (pin "4") (pinfunction "4_4") (pintype "passive"))
    )
    (net (code "96") (name "unconnected-(JP1-Pad6)") (class "Default")
      (node (ref "JP1") (pin "6") (pinfunction "6_6") (pintype "passive"))
    )
    (net (code "97") (name "unconnected-(JP1-Pad7)") (class "Default")
      (node (ref "JP1") (pin "7") (pinfunction "7_7") (pintype "passive"))
    )
    (net (code "98") (name "unconnected-(JP1-Pad8)") (class "Default")
      (node (ref "JP1") (pin "8") (pinfunction "8_8") (pintype "passive"))
    )
    (net (code "99") (name "unconnected-(JP1-Pad9)") (class "Default")
      (node (ref "JP1") (pin "9") (pinfunction "9_9") (pintype "passive"))
    )
    (net (code "100") (name "unconnected-(JP1-Pad11)") (class "Default")
      (node (ref "JP1") (pin "11") (pinfunction "11_11") (pintype "passive"))
    )
    (net (code "101") (name "unconnected-(JP1-Pad18)") (class "Default")
      (node (ref "JP1") (pin "18") (pinfunction "18_18") (pintype "passive"))
    )
    (net (code "102") (name "unconnected-(JP1-Pad19)") (class "Default")
      (node (ref "JP1") (pin "19") (pinfunction "19_19") (pintype "passive"))
    )
    (net (code "103") (name "unconnected-(JP1-Pad20)") (class "Default")
      (node (ref "JP1") (pin "20") (pinfunction "20_20") (pintype "passive"))
    )
    (net (code "104") (name "unconnected-(JP1-Pad22)") (class "Default")
      (node (ref "JP1") (pin "22") (pinfunction "22_22") (pintype "passive"))
    )
    (net (code "105") (name "unconnected-(JP1-Pad23)") (class "Default")
      (node (ref "JP1") (pin "23") (pinfunction "23_23") (pintype "passive"))
    )
    (net (code "106") (name "unconnected-(JP1-Pad24)") (class "Default")
      (node (ref "JP1") (pin "24") (pinfunction "24_24") (pintype "passive"))
    )
    (net (code "107") (name "unconnected-(JP1-Pad25)") (class "Default")
      (node (ref "JP1") (pin "25") (pinfunction "25_25") (pintype "passive"))
    )
    (net (code "108") (name "unconnected-(JP1-Pad27)") (class "Default")
      (node (ref "JP1") (pin "27") (pinfunction "27_27") (pintype "passive"))
    )
    (net (code "109") (name "unconnected-(JP1-Pad28)") (class "Default")
      (node (ref "JP1") (pin "28") (pinfunction "28_28") (pintype "passive"))
    )
    (net (code "110") (name "unconnected-(JP1-Pad29)") (class "Default")
      (node (ref "JP1") (pin "29") (pinfunction "29_29") (pintype "passive"))
    )
    (net (code "111") (name "unconnected-(JP1-Pad30)") (class "Default")
      (node (ref "JP1") (pin "30") (pinfunction "30_30") (pintype "passive"))
    )
    (net (code "112") (name "unconnected-(JP3-Pad12)") (class "Default")
      (node (ref "JP3") (pin "12") (pinfunction "12_12") (pintype "passive"))
    )
    (net (code "113") (name "unconnected-(JP3-Pad14)") (class "Default")
      (node (ref "JP3") (pin "14") (pinfunction "14_14") (pintype "passive"))
    )
    (net (code "114") (name "unconnected-(JP3-Pad16)") (class "Default")
      (node (ref "JP3") (pin "16") (pinfunction "16_16") (pintype "passive"))
    )
    (net (code "115") (name "unconnected-(JP3-Pad17)") (class "Default")
      (node (ref "JP3") (pin "17") (pinfunction "17_17") (pintype "passive"))
    )
    (net (code "116") (name "unconnected-(JP3-Pad18)") (class "Default")
      (node (ref "JP3") (pin "18") (pinfunction "18_18") (pintype "passive"))
    )
    (net (code "117") (name "unconnected-(U1-EN-Pad7)") (class "Default")
      (node (ref "U1") (pin "7") (pinfunction "EN_7") (pintype "bidirectional"))
    )
    (net (code "118") (name "unconnected-(U1-NC-Pad5)") (class "Default")
      (node (ref "U1") (pin "5") (pinfunction "NC_5") (pintype "no_connect"))
    )
  )
)
